# divider.net
KiCad netlist of a schematic drawn in EAGLE
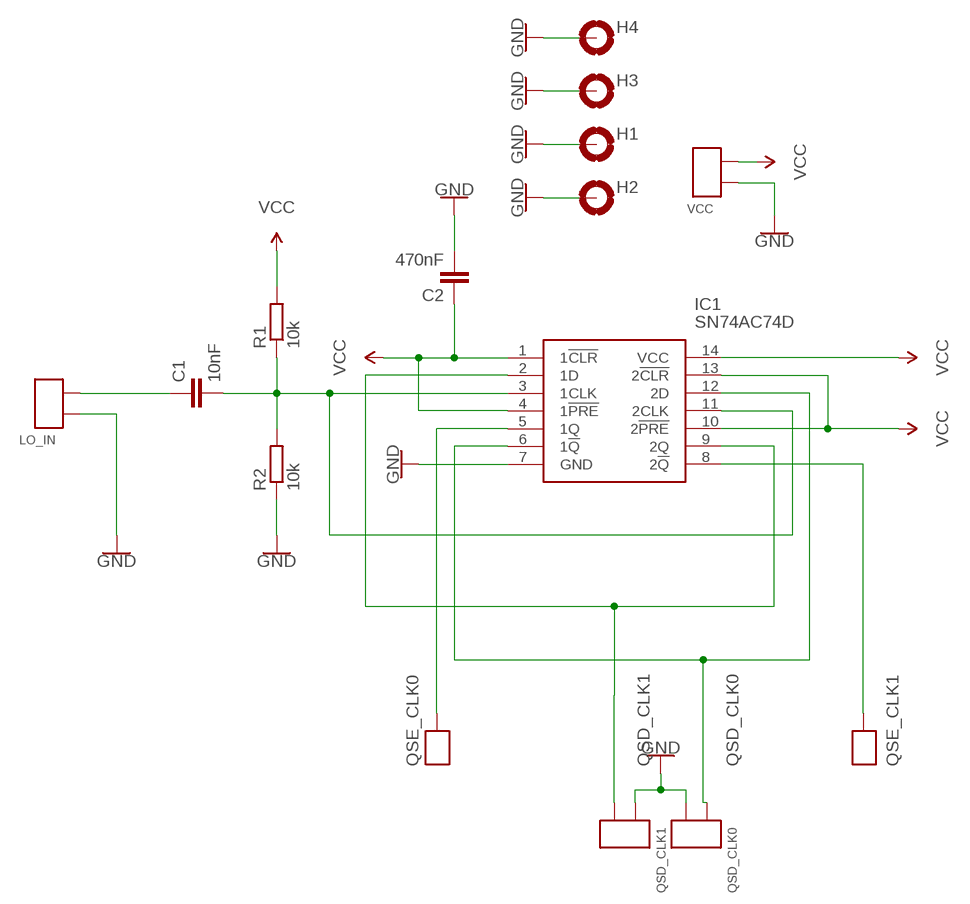
[diagram p0: schematic, sheet 1]

(export (version "E")
  (design (tool "Eeschema 10.0.6"))
  (components
    (comp (ref "C1")
      (value "10nF")
      (footprint "eagle-import:C0805")
      (libsource (lib "eagle-import") (part "C_0805_SMD"))
    )
    (comp (ref "C2")
      (value "470nF")
      (footprint "eagle-import:C0805")
      (libsource (lib "eagle-import") (part "C_0805_SMD"))
    )
    (comp (ref "H1")
      (value "MOUNT-PAD-ROUND3.0")
      (footprint "eagle-import:3,0-PAD")
      (libsource (lib "eagle-import") (part "MOUNT-PAD-ROUND3.0"))
    )
    (comp (ref "H2")
      (value "MOUNT-PAD-ROUND3.0")
      (footprint "eagle-import:3,0-PAD")
      (libsource (lib "eagle-import") (part "MOUNT-PAD-ROUND3.0"))
    )
    (comp (ref "H3")
      (value "MOUNT-PAD-ROUND2.8")
      (footprint "eagle-import:2,8-PAD")
      (libsource (lib "eagle-import") (part "MOUNT-PAD-ROUND2.8"))
    )
    (comp (ref "H4")
      (value "MOUNT-PAD-ROUND2.8")
      (footprint "eagle-import:2,8-PAD")
      (libsource (lib "eagle-import") (part "MOUNT-PAD-ROUND2.8"))
    )
    (comp (ref "IC1")
      (value "SN74AC74D")
      (footprint "eagle-import:SOIC127P600X175-14N")
      (fields (field (name "MOUSER_PART_NUMBER") "595-SN74AC74D"))
      (libsource (lib "eagle-import") (part "SN74AC74D"))
    )
    (comp (ref "LO_IN")
      (value "2X_SMD_PTH_PIN")
      (footprint "eagle-import:2X_SMD_PTH")
      (libsource (lib "eagle-import") (part "2X_SMD_PTH_PIN"))
    )
    (comp (ref "QSD_CLK0")
      (value "2X_SMD_PTH_PIN")
      (footprint "eagle-import:2X_SMD_PTH")
      (libsource (lib "eagle-import") (part "2X_SMD_PTH_PIN"))
    )
    (comp (ref "QSD_CLK1")
      (value "2X_SMD_PTH_PIN")
      (footprint "eagle-import:2X_SMD_PTH")
      (libsource (lib "eagle-import") (part "2X_SMD_PTH_PIN"))
    )
    (comp (ref "R1")
      (value "10k")
      (footprint "eagle-import:R0805W")
      (libsource (lib "eagle-import") (part "R_0805_SMD"))
    )
    (comp (ref "R2")
      (value "10k")
      (footprint "eagle-import:R0805W")
      (libsource (lib "eagle-import") (part "R_0805_SMD"))
    )
    (comp (ref "TX_CLK0")
      (value "SMD_PTH_PIN")
      (footprint "eagle-import:SMD_PTH_PIN")
      (libsource (lib "eagle-import") (part "SMD_PTH_PIN"))
    )
    (comp (ref "TX_CLK1")
      (value "SMD_PTH_PIN")
      (footprint "eagle-import:SMD_PTH_PIN")
      (libsource (lib "eagle-import") (part "SMD_PTH_PIN"))
    )
    (comp (ref "VCC")
      (value "2X_SMD_PTH_PIN")
      (footprint "eagle-import:2X_SMD_PTH")
      (libsource (lib "eagle-import") (part "2X_SMD_PTH_PIN"))
    )
  )
  (nets
    (net (code "1") (name "/QSD_CLK0") (class "Default")
      (node (ref "IC1") (pin "12") (pinfunction "2D_12") (pintype "bidirectional"))
      (node (ref "IC1") (pin "6") (pinfunction "1~{Q}_6") (pintype "bidirectional"))
      (node (ref "QSD_CLK0") (pin "P$1") (pinfunction "PIN0_P$1") (pintype "bidirectional"))
      (node (ref "QSD_CLK0") (pin "T$1") (pinfunction "PIN0_T$1") (pintype "bidirectional"))
    )
    (net (code "2") (name "/QSD_CLK1") (class "Default")
      (node (ref "IC1") (pin "2") (pinfunction "1D_2") (pintype "bidirectional"))
      (node (ref "IC1") (pin "9") (pinfunction "2Q_9") (pintype "bidirectional"))
      (node (ref "QSD_CLK1") (pin "P$2") (pinfunction "PIN1_P$2") (pintype "bidirectional"))
      (node (ref "QSD_CLK1") (pin "T$2") (pinfunction "PIN1_T$2") (pintype "bidirectional"))
    )
    (net (code "3") (name "/QSE_CLK0") (class "Default")
      (node (ref "IC1") (pin "5") (pinfunction "1Q_5") (pintype "bidirectional"))
      (node (ref "TX_CLK0") (pin "P$1") (pinfunction "P$1_P$1") (pintype "bidirectional"))
      (node (ref "TX_CLK0") (pin "P$2") (pinfunction "P$1_P$2") (pintype "bidirectional"))
    )
    (net (code "4") (name "/QSE_CLK1") (class "Default")
      (node (ref "IC1") (pin "8") (pinfunction "2~{Q}_8") (pintype "bidirectional"))
      (node (ref "TX_CLK1") (pin "P$1") (pinfunction "P$1_P$1") (pintype "bidirectional"))
      (node (ref "TX_CLK1") (pin "P$2") (pinfunction "P$1_P$2") (pintype "bidirectional"))
    )
    (net (code "5") (name "GND") (class "Default")
      (node (ref "C2") (pin "2") (pinfunction "2_2") (pintype "passive"))
      (node (ref "H1") (pin "B3,0") (pinfunction "MOUNT_B3,0") (pintype "passive"))
      (node (ref "H2") (pin "B3,0") (pinfunction "MOUNT_B3,0") (pintype "passive"))
      (node (ref "H3") (pin "B2,8") (pinfunction "MOUNT_B2,8") (pintype "passive"))
      (node (ref "H4") (pin "B2,8") (pinfunction "MOUNT_B2,8") (pintype "passive"))
      (node (ref "IC1") (pin "7") (pinfunction "GND_7") (pintype "bidirectional"))
      (node (ref "LO_IN") (pin "P$1") (pinfunction "PIN0_P$1") (pintype "bidirectional"))
      (node (ref "LO_IN") (pin "T$1") (pinfunction "PIN0_T$1") (pintype "bidirectional"))
      (node (ref "QSD_CLK0") (pin "P$2") (pinfunction "PIN1_P$2") (pintype "bidirectional"))
      (node (ref "QSD_CLK0") (pin "T$2") (pinfunction "PIN1_T$2") (pintype "bidirectional"))
      (node (ref "QSD_CLK1") (pin "P$1") (pinfunction "PIN0_P$1") (pintype "bidirectional"))
      (node (ref "QSD_CLK1") (pin "T$1") (pinfunction "PIN0_T$1") (pintype "bidirectional"))
      (node (ref "R2") (pin "1") (pinfunction "1_1") (pintype "passive"))
      (node (ref "VCC") (pin "P$1") (pinfunction "PIN0_P$1") (pintype "bidirectional"))
      (node (ref "VCC") (pin "T$1") (pinfunction "PIN0_T$1") (pintype "bidirectional"))
    )
    (net (code "6") (name "Net-(C1-Pad1)") (class "Default")
      (node (ref "C1") (pin "1") (pinfunction "1_1") (pintype "passive"))
      (node (ref "LO_IN") (pin "P$2") (pinfunction "PIN1_P$2") (pintype "bidirectional"))
      (node (ref "LO_IN") (pin "T$2") (pinfunction "PIN1_T$2") (pintype "bidirectional"))
    )
    (net (code "7") (name "Net-(IC1-1CLK)") (class "Default")
      (node (ref "C1") (pin "2") (pinfunction "2_2") (pintype "passive"))
      (node (ref "IC1") (pin "11") (pinfunction "2CLK_11") (pintype "bidirectional"))
      (node (ref "IC1") (pin "3") (pinfunction "1CLK_3") (pintype "bidirectional"))
      (node (ref "R1") (pin "1") (pinfunction "1_1") (pintype "passive"))
      (node (ref "R2") (pin "2") (pinfunction "2_2") (pintype "passive"))
    )
    (net (code "8") (name "VCC") (class "Default")
      (node (ref "C2") (pin "1") (pinfunction "1_1") (pintype "passive"))
      (node (ref "IC1") (pin "1") (pinfunction "1~{CLR}_1") (pintype "bidirectional"))
      (node (ref "IC1") (pin "10") (pinfunction "2~{PRE}_10") (pintype "bidirectional"))
      (node (ref "IC1") (pin "13") (pinfunction "2~{CLR}_13") (pintype "bidirectional"))
      (node (ref "IC1") (pin "14") (pinfunction "VCC_14") (pintype "bidirectional"))
      (node (ref "IC1") (pin "4") (pinfunction "1~{PRE}_4") (pintype "bidirectional"))
      (node (ref "R1") (pin "2") (pinfunction "2_2") (pintype "passive"))
      (node (ref "VCC") (pin "P$2") (pinfunction "PIN1_P$2") (pintype "bidirectional"))
      (node (ref "VCC") (pin "T$2") (pinfunction "PIN1_T$2") (pintype "bidirectional"))
    )
  )
)
